# 1_P1.net
KiCad netlist of a schematic drawn in Altium Designer
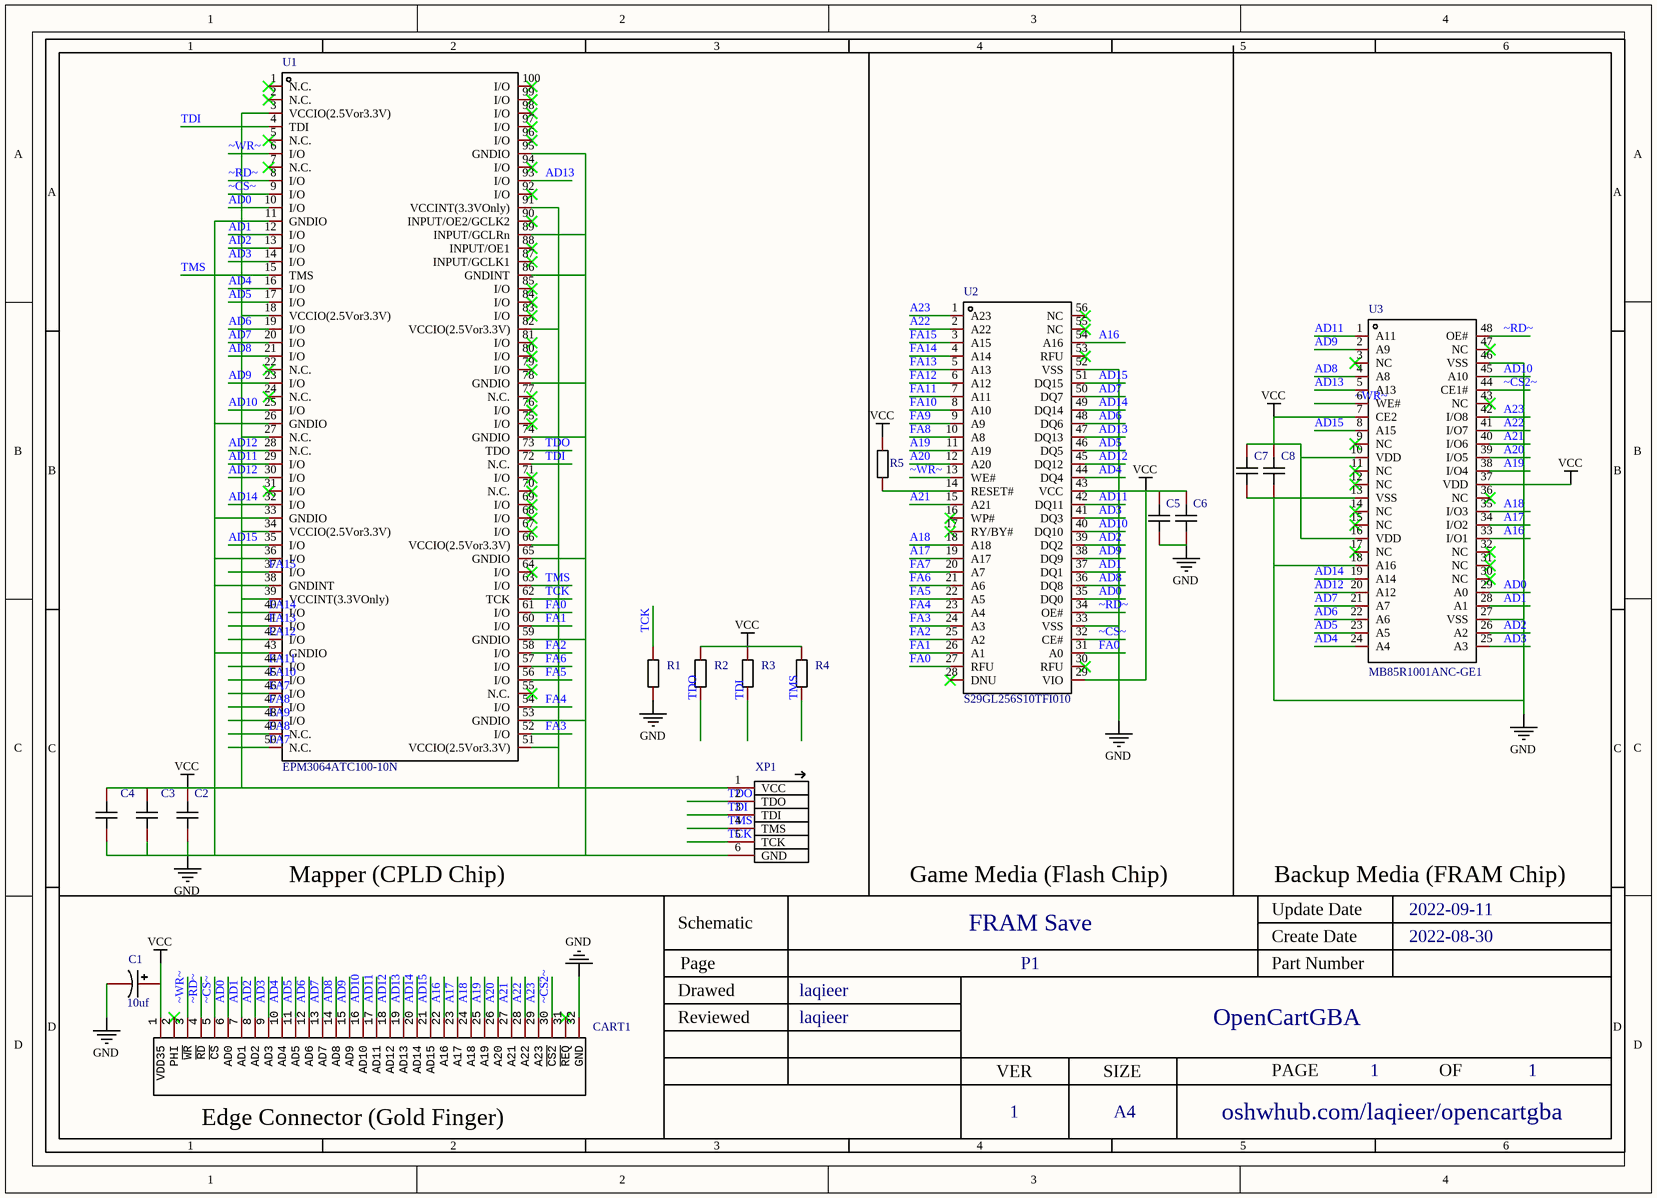
[diagram p0: 1_P1.schdoc]

(export (version "E")
  (design (tool "Eeschema 10.0.6"))
  (components
    (comp (ref "C1")
      (value "10uf")
      (fields (field (name "NAME") "10uf"))
      (libsource (lib "altium-import") (part "root_2_10uf_"))
    )
    (comp (ref "C2")
      (value "100nF/0603/50V")
      (libsource (lib "altium-import") (part "root_3_100nF/0603/50V_"))
    )
    (comp (ref "C3")
      (value "100nF/0603/50V")
      (libsource (lib "altium-import") (part "root_1_100nF/0603/50V_"))
    )
    (comp (ref "C4")
      (value "100nF/0603/50V")
      (libsource (lib "altium-import") (part "root_1_100nF/0603/50V_"))
    )
    (comp (ref "C5")
      (value "100nF/0603/50V")
      (libsource (lib "altium-import") (part "root_1_100nF/0603/50V_"))
    )
    (comp (ref "C6")
      (value "100nF/0603/50V")
      (libsource (lib "altium-import") (part "root_1_100nF/0603/50V_"))
    )
    (comp (ref "C7")
      (value "100nF/0603/50V")
      (libsource (lib "altium-import") (part "root_1_100nF/0603/50V_"))
    )
    (comp (ref "C8")
      (value "100nF/0603/50V")
      (libsource (lib "altium-import") (part "root_1_100nF/0603/50V_"))
    )
    (comp (ref "CART1")
      (value "GBACartridge")
      (description "GBA Cartridge")
      (libsource (lib "altium-import") (part "root_0_GBACartridge_"))
    )
    (comp (ref "R1")
      (value "10kω")
      (description "电阻类型:薄膜电阻;阻值:10kΩ;精度:±0.1%;功率:100mW;温度系数:±25ppm/;最大工作电压:75V;工作温度范围:-55~+155;")
      (fields
        (field (name "MANUFACTURER") "EVER OHMS(天二科技)")
        (field (name "MANUFACTURER PART") "TR0603B10K0P0525Z")
      )
      (libsource (lib "altium-import") (part "root_1_10kω_"))
    )
    (comp (ref "R2")
      (value "10kω")
      (description "电阻类型:薄膜电阻;阻值:10kΩ;精度:±0.1%;功率:100mW;温度系数:±25ppm/;最大工作电压:75V;工作温度范围:-55~+155;")
      (fields
        (field (name "MANUFACTURER") "EVER OHMS(天二科技)")
        (field (name "MANUFACTURER PART") "TR0603B10K0P0525Z")
      )
      (libsource (lib "altium-import") (part "root_1_10kω_"))
    )
    (comp (ref "R3")
      (value "10kω")
      (description "电阻类型:薄膜电阻;阻值:10kΩ;精度:±0.1%;功率:100mW;温度系数:±25ppm/;最大工作电压:75V;工作温度范围:-55~+155;")
      (fields
        (field (name "MANUFACTURER") "EVER OHMS(天二科技)")
        (field (name "MANUFACTURER PART") "TR0603B10K0P0525Z")
      )
      (libsource (lib "altium-import") (part "root_1_10kω_"))
    )
    (comp (ref "R4")
      (value "10kω")
      (description "电阻类型:薄膜电阻;阻值:10kΩ;精度:±0.1%;功率:100mW;温度系数:±25ppm/;最大工作电压:75V;工作温度范围:-55~+155;")
      (fields
        (field (name "MANUFACTURER") "EVER OHMS(天二科技)")
        (field (name "MANUFACTURER PART") "TR0603B10K0P0525Z")
      )
      (libsource (lib "altium-import") (part "root_1_10kω_"))
    )
    (comp (ref "R5")
      (value "10kω")
      (description "电阻类型:薄膜电阻;阻值:10kΩ;精度:±0.1%;功率:100mW;温度系数:±25ppm/;最大工作电压:75V;工作温度范围:-55~+155;")
      (fields
        (field (name "MANUFACTURER") "EVER OHMS(天二科技)")
        (field (name "MANUFACTURER PART") "TR0603B10K0P0525Z")
      )
      (libsource (lib "altium-import") (part "root_1_10kω_"))
    )
    (comp (ref "U1")
      (value "EPM3064ATC100-10N")
      (description "可编程类型:-;逻辑元件/块数:-;宏单元数:-;I/O 数:-;工作温度:-;")
      (fields (field (name "NAME") "EPM3064ATC100-10N") (field (name "MANUFACTURER") "Intel/Altera"))
      (libsource (lib "altium-import") (part "root_0_EPM3064ATC100-10N_"))
    )
    (comp (ref "U2")
      (value "S29GL256S10TFI010")
      (fields (field (name "NAME") "S29GL256S10TFI010") (field (name "MANUFACTURER") "SPANSION(飞索)"))
      (libsource (lib "altium-import") (part "root_0_S29GL256S10TFI010_"))
    )
    (comp (ref "U3")
      (value "MB85R1001ANC-GE1")
      (description "存储器容量:1Mb (128K x 8);存储器接口类型:Parallel;工作电压:3V ~ 3.6V;")
      (fields (field (name "NAME") "MB85R1001ANC-GE1") (field (name "MANUFACTURER") "FUJITSU(富士通)"))
      (libsource (lib "altium-import") (part "root_0_MB85R1001ANC-GE1_"))
    )
    (comp (ref "XP1") (value "jtag") (libsource (lib "altium-import") (part "root_0_jtag_")))
  )
  (nets
    (net (code "1") (name "/A16") (class "Default")
      (node (ref "CART1") (pin "22") (pinfunction "A16_22") (pintype "passive"))
      (node (ref "U2") (pin "54") (pinfunction "A16_54") (pintype "passive"))
      (node (ref "U3") (pin "33") (pinfunction "I/O1_33") (pintype "passive"))
    )
    (net (code "2") (name "/A17") (class "Default")
      (node (ref "CART1") (pin "23") (pinfunction "A17_23") (pintype "passive"))
      (node (ref "U2") (pin "19") (pinfunction "A17_19") (pintype "passive"))
      (node (ref "U3") (pin "34") (pinfunction "I/O2_34") (pintype "passive"))
    )
    (net (code "3") (name "/A18") (class "Default")
      (node (ref "CART1") (pin "24") (pinfunction "A18_24") (pintype "passive"))
      (node (ref "U2") (pin "18") (pinfunction "A18_18") (pintype "passive"))
      (node (ref "U3") (pin "35") (pinfunction "I/O3_35") (pintype "passive"))
    )
    (net (code "4") (name "/A19") (class "Default")
      (node (ref "CART1") (pin "25") (pinfunction "A19_25") (pintype "passive"))
      (node (ref "U2") (pin "11") (pinfunction "A19_11") (pintype "passive"))
      (node (ref "U3") (pin "38") (pinfunction "I/O4_38") (pintype "passive"))
    )
    (net (code "5") (name "/A20") (class "Default")
      (node (ref "CART1") (pin "26") (pinfunction "A20_26") (pintype "passive"))
      (node (ref "U2") (pin "12") (pinfunction "A20_12") (pintype "passive"))
      (node (ref "U3") (pin "39") (pinfunction "I/O5_39") (pintype "passive"))
    )
    (net (code "6") (name "/A21") (class "Default")
      (node (ref "CART1") (pin "27") (pinfunction "A21_27") (pintype "passive"))
      (node (ref "U2") (pin "15") (pinfunction "A21_15") (pintype "passive"))
      (node (ref "U3") (pin "40") (pinfunction "I/O6_40") (pintype "passive"))
    )
    (net (code "7") (name "/A22") (class "Default")
      (node (ref "CART1") (pin "28") (pinfunction "A22_28") (pintype "passive"))
      (node (ref "U2") (pin "2") (pinfunction "A22_2") (pintype "passive"))
      (node (ref "U3") (pin "41") (pinfunction "I/O7_41") (pintype "passive"))
    )
    (net (code "8") (name "/A23") (class "Default")
      (node (ref "CART1") (pin "29") (pinfunction "A23_29") (pintype "passive"))
      (node (ref "U2") (pin "1") (pinfunction "A23_1") (pintype "passive"))
      (node (ref "U3") (pin "42") (pinfunction "I/O8_42") (pintype "passive"))
    )
    (net (code "9") (name "/AD0") (class "Default")
      (node (ref "CART1") (pin "6") (pinfunction "AD0_6") (pintype "passive"))
      (node (ref "U1") (pin "10") (pinfunction "I/O_10") (pintype "passive"))
      (node (ref "U2") (pin "35") (pinfunction "DQ0_35") (pintype "passive"))
      (node (ref "U3") (pin "29") (pinfunction "A0_29") (pintype "passive"))
    )
    (net (code "10") (name "/AD1") (class "Default")
      (node (ref "CART1") (pin "7") (pinfunction "AD1_7") (pintype "passive"))
      (node (ref "U1") (pin "12") (pinfunction "I/O_12") (pintype "passive"))
      (node (ref "U2") (pin "37") (pinfunction "DQ1_37") (pintype "passive"))
      (node (ref "U3") (pin "28") (pinfunction "A1_28") (pintype "passive"))
    )
    (net (code "11") (name "/AD2") (class "Default")
      (node (ref "CART1") (pin "8") (pinfunction "AD2_8") (pintype "passive"))
      (node (ref "U1") (pin "13") (pinfunction "I/O_13") (pintype "passive"))
      (node (ref "U2") (pin "39") (pinfunction "DQ2_39") (pintype "passive"))
      (node (ref "U3") (pin "26") (pinfunction "A2_26") (pintype "passive"))
    )
    (net (code "12") (name "/AD3") (class "Default")
      (node (ref "CART1") (pin "9") (pinfunction "AD3_9") (pintype "passive"))
      (node (ref "U1") (pin "14") (pinfunction "I/O_14") (pintype "passive"))
      (node (ref "U2") (pin "41") (pinfunction "DQ3_41") (pintype "passive"))
      (node (ref "U3") (pin "25") (pinfunction "A3_25") (pintype "passive"))
    )
    (net (code "13") (name "/AD4") (class "Default")
      (node (ref "CART1") (pin "10") (pinfunction "AD4_10") (pintype "passive"))
      (node (ref "U1") (pin "16") (pinfunction "I/O_16") (pintype "passive"))
      (node (ref "U2") (pin "44") (pinfunction "DQ4_44") (pintype "passive"))
      (node (ref "U3") (pin "24") (pinfunction "A4_24") (pintype "passive"))
    )
    (net (code "14") (name "/AD5") (class "Default")
      (node (ref "CART1") (pin "11") (pinfunction "AD5_11") (pintype "passive"))
      (node (ref "U1") (pin "17") (pinfunction "I/O_17") (pintype "passive"))
      (node (ref "U2") (pin "46") (pinfunction "DQ5_46") (pintype "passive"))
      (node (ref "U3") (pin "23") (pinfunction "A5_23") (pintype "passive"))
    )
    (net (code "15") (name "/AD6") (class "Default")
      (node (ref "CART1") (pin "12") (pinfunction "AD6_12") (pintype "passive"))
      (node (ref "U1") (pin "19") (pinfunction "I/O_19") (pintype "passive"))
      (node (ref "U2") (pin "48") (pinfunction "DQ6_48") (pintype "passive"))
      (node (ref "U3") (pin "22") (pinfunction "A6_22") (pintype "passive"))
    )
    (net (code "16") (name "/AD7") (class "Default")
      (node (ref "CART1") (pin "13") (pinfunction "AD7_13") (pintype "passive"))
      (node (ref "U1") (pin "20") (pinfunction "I/O_20") (pintype "passive"))
      (node (ref "U2") (pin "50") (pinfunction "DQ7_50") (pintype "passive"))
      (node (ref "U3") (pin "21") (pinfunction "A7_21") (pintype "passive"))
    )
    (net (code "17") (name "/AD8") (class "Default")
      (node (ref "CART1") (pin "14") (pinfunction "AD8_14") (pintype "passive"))
      (node (ref "U1") (pin "21") (pinfunction "I/O_21") (pintype "passive"))
      (node (ref "U2") (pin "36") (pinfunction "DQ8_36") (pintype "passive"))
      (node (ref "U3") (pin "4") (pinfunction "A8_4") (pintype "passive"))
    )
    (net (code "18") (name "/AD9") (class "Default")
      (node (ref "CART1") (pin "15") (pinfunction "AD9_15") (pintype "passive"))
      (node (ref "U1") (pin "23") (pinfunction "I/O_23") (pintype "passive"))
      (node (ref "U2") (pin "38") (pinfunction "DQ9_38") (pintype "passive"))
      (node (ref "U3") (pin "2") (pinfunction "A9_2") (pintype "passive"))
    )
    (net (code "19") (name "/AD10") (class "Default")
      (node (ref "CART1") (pin "16") (pinfunction "AD10_16") (pintype "passive"))
      (node (ref "U1") (pin "25") (pinfunction "I/O_25") (pintype "passive"))
      (node (ref "U2") (pin "40") (pinfunction "DQ10_40") (pintype "passive"))
      (node (ref "U3") (pin "45") (pinfunction "A10_45") (pintype "passive"))
    )
    (net (code "20") (name "/AD11") (class "Default")
      (node (ref "CART1") (pin "17") (pinfunction "AD11_17") (pintype "passive"))
      (node (ref "U1") (pin "29") (pinfunction "I/O_29") (pintype "passive"))
      (node (ref "U2") (pin "42") (pinfunction "DQ11_42") (pintype "passive"))
      (node (ref "U3") (pin "1") (pinfunction "A11_1") (pintype "passive"))
    )
    (net (code "21") (name "/AD12") (class "Default")
      (node (ref "CART1") (pin "18") (pinfunction "AD12_18") (pintype "passive"))
      (node (ref "U1") (pin "28") (pinfunction "N.C._28") (pintype "passive"))
      (node (ref "U1") (pin "30") (pinfunction "I/O_30") (pintype "passive"))
      (node (ref "U2") (pin "45") (pinfunction "DQ12_45") (pintype "passive"))
      (node (ref "U3") (pin "20") (pinfunction "A12_20") (pintype "passive"))
    )
    (net (code "22") (name "/AD13") (class "Default")
      (node (ref "CART1") (pin "19") (pinfunction "AD13_19") (pintype "passive"))
      (node (ref "U1") (pin "93") (pinfunction "I/O_93") (pintype "passive"))
      (node (ref "U2") (pin "47") (pinfunction "DQ13_47") (pintype "passive"))
      (node (ref "U3") (pin "5") (pinfunction "A13_5") (pintype "passive"))
    )
    (net (code "23") (name "/AD14") (class "Default")
      (node (ref "CART1") (pin "20") (pinfunction "AD14_20") (pintype "passive"))
      (node (ref "U1") (pin "32") (pinfunction "I/O_32") (pintype "passive"))
      (node (ref "U2") (pin "49") (pinfunction "DQ14_49") (pintype "passive"))
      (node (ref "U3") (pin "19") (pinfunction "A14_19") (pintype "passive"))
    )
    (net (code "24") (name "/AD15") (class "Default")
      (node (ref "CART1") (pin "21") (pinfunction "AD15_21") (pintype "passive"))
      (node (ref "U1") (pin "35") (pinfunction "I/O_35") (pintype "passive"))
      (node (ref "U2") (pin "51") (pinfunction "DQ15_51") (pintype "passive"))
      (node (ref "U3") (pin "8") (pinfunction "A15_8") (pintype "passive"))
    )
    (net (code "25") (name "/FA0") (class "Default")
      (node (ref "U1") (pin "61") (pinfunction "I/O_61") (pintype "passive"))
      (node (ref "U2") (pin "27") (pinfunction "RFU_27") (pintype "passive"))
      (node (ref "U2") (pin "31") (pinfunction "A0_31") (pintype "passive"))
    )
    (net (code "26") (name "/FA1") (class "Default")
      (node (ref "U1") (pin "60") (pinfunction "I/O_60") (pintype "passive"))
      (node (ref "U2") (pin "26") (pinfunction "A1_26") (pintype "passive"))
    )
    (net (code "27") (name "/FA2") (class "Default")
      (node (ref "U1") (pin "58") (pinfunction "I/O_58") (pintype "passive"))
      (node (ref "U2") (pin "25") (pinfunction "A2_25") (pintype "passive"))
    )
    (net (code "28") (name "/FA3") (class "Default")
      (node (ref "U1") (pin "52") (pinfunction "I/O_52") (pintype "passive"))
      (node (ref "U2") (pin "24") (pinfunction "A3_24") (pintype "passive"))
    )
    (net (code "29") (name "/FA4") (class "Default")
      (node (ref "U1") (pin "54") (pinfunction "I/O_54") (pintype "passive"))
      (node (ref "U2") (pin "23") (pinfunction "A4_23") (pintype "passive"))
    )
    (net (code "30") (name "/FA5") (class "Default")
      (node (ref "U1") (pin "56") (pinfunction "I/O_56") (pintype "passive"))
      (node (ref "U2") (pin "22") (pinfunction "A5_22") (pintype "passive"))
    )
    (net (code "31") (name "/FA6") (class "Default")
      (node (ref "U1") (pin "57") (pinfunction "I/O_57") (pintype "passive"))
      (node (ref "U2") (pin "21") (pinfunction "A6_21") (pintype "passive"))
    )
    (net (code "32") (name "/FA7") (class "Default")
      (node (ref "U1") (pin "46") (pinfunction "I/O_46") (pintype "passive"))
      (node (ref "U1") (pin "50") (pinfunction "N.C._50") (pintype "passive"))
      (node (ref "U2") (pin "20") (pinfunction "A7_20") (pintype "passive"))
    )
    (net (code "33") (name "/FA8") (class "Default")
      (node (ref "U1") (pin "47") (pinfunction "I/O_47") (pintype "passive"))
      (node (ref "U1") (pin "49") (pinfunction "N.C._49") (pintype "passive"))
      (node (ref "U2") (pin "10") (pinfunction "A8_10") (pintype "passive"))
    )
    (net (code "34") (name "/FA9") (class "Default")
      (node (ref "U1") (pin "48") (pinfunction "I/O_48") (pintype "passive"))
      (node (ref "U2") (pin "9") (pinfunction "A9_9") (pintype "passive"))
    )
    (net (code "35") (name "/FA10") (class "Default")
      (node (ref "U1") (pin "45") (pinfunction "I/O_45") (pintype "passive"))
      (node (ref "U2") (pin "8") (pinfunction "A10_8") (pintype "passive"))
    )
    (net (code "36") (name "/FA11") (class "Default")
      (node (ref "U1") (pin "44") (pinfunction "I/O_44") (pintype "passive"))
      (node (ref "U2") (pin "7") (pinfunction "A11_7") (pintype "passive"))
    )
    (net (code "37") (name "/FA12") (class "Default")
      (node (ref "U1") (pin "42") (pinfunction "I/O_42") (pintype "passive"))
      (node (ref "U2") (pin "6") (pinfunction "A12_6") (pintype "passive"))
    )
    (net (code "38") (name "/FA13") (class "Default")
      (node (ref "U1") (pin "41") (pinfunction "I/O_41") (pintype "passive"))
      (node (ref "U2") (pin "5") (pinfunction "A13_5") (pintype "passive"))
    )
    (net (code "39") (name "/FA14") (class "Default")
      (node (ref "U1") (pin "40") (pinfunction "I/O_40") (pintype "passive"))
      (node (ref "U2") (pin "4") (pinfunction "A14_4") (pintype "passive"))
    )
    (net (code "40") (name "/FA15") (class "Default")
      (node (ref "U1") (pin "37") (pinfunction "I/O_37") (pintype "passive"))
      (node (ref "U2") (pin "3") (pinfunction "A15_3") (pintype "passive"))
    )
    (net (code "41") (name "/TCK") (class "Default")
      (node (ref "R1") (pin "2") (pinfunction "2_2") (pintype "passive"))
      (node (ref "U1") (pin "62") (pinfunction "TCK_62") (pintype "passive"))
      (node (ref "XP1") (pin "5") (pinfunction "TCK_5") (pintype "passive"))
    )
    (net (code "42") (name "/TDI") (class "Default")
      (node (ref "R3") (pin "1") (pinfunction "1_1") (pintype "passive"))
      (node (ref "U1") (pin "4") (pinfunction "TDI_4") (pintype "passive"))
      (node (ref "U1") (pin "72") (pinfunction "N.C._72") (pintype "passive"))
      (node (ref "XP1") (pin "3") (pinfunction "TDI_3") (pintype "passive"))
    )
    (net (code "43") (name "/TDO") (class "Default")
      (node (ref "R2") (pin "1") (pinfunction "1_1") (pintype "passive"))
      (node (ref "U1") (pin "73") (pinfunction "TDO_73") (pintype "passive"))
      (node (ref "XP1") (pin "2") (pinfunction "TDO_2") (pintype "passive"))
    )
    (net (code "44") (name "/TMS") (class "Default")
      (node (ref "R4") (pin "1") (pinfunction "1_1") (pintype "passive"))
      (node (ref "U1") (pin "15") (pinfunction "TMS_15") (pintype "passive"))
      (node (ref "U1") (pin "63") (pinfunction "I/O_63") (pintype "passive"))
      (node (ref "XP1") (pin "4") (pinfunction "TMS_4") (pintype "passive"))
    )
    (net (code "45") (name "/~CS2~") (class "Default")
      (node (ref "CART1") (pin "30") (pinfunction "~{CS2}_30") (pintype "passive"))
      (node (ref "U3") (pin "44") (pinfunction "CE1#_44") (pintype "passive"))
    )
    (net (code "46") (name "/~CS~") (class "Default")
      (node (ref "CART1") (pin "5") (pinfunction "~{CS}_5") (pintype "passive"))
      (node (ref "U1") (pin "9") (pinfunction "I/O_9") (pintype "passive"))
      (node (ref "U2") (pin "32") (pinfunction "CE#_32") (pintype "passive"))
    )
    (net (code "47") (name "/~RD~") (class "Default")
      (node (ref "CART1") (pin "4") (pinfunction "~{RD}_4") (pintype "passive"))
      (node (ref "U1") (pin "8") (pinfunction "I/O_8") (pintype "passive"))
      (node (ref "U2") (pin "34") (pinfunction "OE#_34") (pintype "passive"))
      (node (ref "U3") (pin "48") (pinfunction "OE#_48") (pintype "passive"))
    )
    (net (code "48") (name "/~WR~") (class "Default")
      (node (ref "CART1") (pin "3") (pinfunction "~{WR}_3") (pintype "passive"))
      (node (ref "U1") (pin "6") (pinfunction "I/O_6") (pintype "passive"))
      (node (ref "U2") (pin "13") (pinfunction "WE#_13") (pintype "passive"))
      (node (ref "U3") (pin "6") (pinfunction "WE#_6") (pintype "passive"))
    )
    (net (code "49") (name "GND") (class "Default")
      (node (ref "C1") (pin "2") (pinfunction "2_2") (pintype "passive"))
      (node (ref "C2") (pin "1") (pinfunction "1_1") (pintype "passive"))
      (node (ref "C3") (pin "2") (pinfunction "2_2") (pintype "passive"))
      (node (ref "C4") (pin "2") (pinfunction "2_2") (pintype "passive"))
      (node (ref "C5") (pin "2") (pinfunction "2_2") (pintype "passive"))
      (node (ref "C6") (pin "2") (pinfunction "2_2") (pintype "passive"))
      (node (ref "C7") (pin "2") (pinfunction "2_2") (pintype "passive"))
      (node (ref "C8") (pin "2") (pinfunction "2_2") (pintype "passive"))
      (node (ref "CART1") (pin "32") (pinfunction "GND_32") (pintype "passive"))
      (node (ref "R1") (pin "1") (pinfunction "1_1") (pintype "passive"))
      (node (ref "U1") (pin "11") (pinfunction "GNDIO_11") (pintype "passive"))
      (node (ref "U1") (pin "26") (pinfunction "GNDIO_26") (pintype "passive"))
      (node (ref "U1") (pin "33") (pinfunction "GNDIO_33") (pintype "passive"))
      (node (ref "U1") (pin "36") (pinfunction "I/O_36") (pintype "passive"))
      (node (ref "U1") (pin "38") (pinfunction "GNDINT_38") (pintype "passive"))
      (node (ref "U1") (pin "43") (pinfunction "GNDIO_43") (pintype "passive"))
      (node (ref "U1") (pin "53") (pinfunction "GNDIO_53") (pintype "passive"))
      (node (ref "U1") (pin "59") (pinfunction "GNDIO_59") (pintype "passive"))
      (node (ref "U1") (pin "65") (pinfunction "GNDIO_65") (pintype "passive"))
      (node (ref "U1") (pin "74") (pinfunction "GNDIO_74") (pintype "passive"))
      (node (ref "U1") (pin "78") (pinfunction "GNDIO_78") (pintype "passive"))
      (node (ref "U1") (pin "86") (pinfunction "GNDINT_86") (pintype "passive"))
      (node (ref "U1") (pin "89") (pinfunction "INPUT/GCLRn_89") (pintype "passive"))
      (node (ref "U1") (pin "95") (pinfunction "GNDIO_95") (pintype "passive"))
      (node (ref "U2") (pin "33") (pinfunction "VSS_33") (pintype "passive"))
      (node (ref "U2") (pin "52") (pinfunction "VSS_52") (pintype "passive"))
      (node (ref "U3") (pin "13") (pinfunction "VSS_13") (pintype "passive"))
      (node (ref "U3") (pin "18") (pinfunction "A16_18") (pintype "passive"))
      (node (ref "U3") (pin "27") (pinfunction "VSS_27") (pintype "passive"))
      (node (ref "U3") (pin "46") (pinfunction "VSS_46") (pintype "passive"))
      (node (ref "XP1") (pin "6") (pinfunction "GND_6") (pintype "passive"))
    )
    (net (code "50") (name "Net-(U2-RESET#)") (class "Default")
      (node (ref "R5") (pin "1") (pinfunction "1_1") (pintype "passive"))
      (node (ref "U2") (pin "14") (pinfunction "RESET#_14") (pintype "passive"))
    )
    (net (code "51") (name "VCC") (class "Default")
      (node (ref "C1") (pin "1") (pinfunction "1_1") (pintype "passive"))
      (node (ref "C2") (pin "2") (pinfunction "2_2") (pintype "passive"))
      (node (ref "C3") (pin "1") (pinfunction "1_1") (pintype "passive"))
      (node (ref "C4") (pin "1") (pinfunction "1_1") (pintype "passive"))
      (node (ref "C5") (pin "1") (pinfunction "1_1") (pintype "passive"))
      (node (ref "C6") (pin "1") (pinfunction "1_1") (pintype "passive"))
      (node (ref "C7") (pin "1") (pinfunction "1_1") (pintype "passive"))
      (node (ref "C8") (pin "1") (pinfunction "1_1") (pintype "passive"))
      (node (ref "CART1") (pin "1") (pinfunction "VDD35_1") (pintype "passive"))
      (node (ref "R2") (pin "2") (pinfunction "2_2") (pintype "passive"))
      (node (ref "R3") (pin "2") (pinfunction "2_2") (pintype "passive"))
      (node (ref "R4") (pin "2") (pinfunction "2_2") (pintype "passive"))
      (node (ref "R5") (pin "2") (pinfunction "2_2") (pintype "passive"))
      (node (ref "U1") (pin "18") (pinfunction "VCCIO(2.5Vor3.3V)_18") (pintype "passive"))
      (node (ref "U1") (pin "27") (pinfunction "N.C._27") (pintype "passive"))
      (node (ref "U1") (pin "3") (pinfunction "VCCIO(2.5Vor3.3V)_3") (pintype "passive"))
      (node (ref "U1") (pin "34") (pinfunction "VCCIO(2.5Vor3.3V)_34") (pintype "passive"))
      (node (ref "U1") (pin "39") (pinfunction "VCCINT(3.3VOnly)_39") (pintype "passive"))
      (node (ref "U1") (pin "51") (pinfunction "VCCIO(2.5Vor3.3V)_51") (pintype "passive"))
      (node (ref "U1") (pin "66") (pinfunction "VCCIO(2.5Vor3.3V)_66") (pintype "passive"))
      (node (ref "U1") (pin "82") (pinfunction "VCCIO(2.5Vor3.3V)_82") (pintype "passive"))
      (node (ref "U1") (pin "91") (pinfunction "VCCINT(3.3VOnly)_91") (pintype "passive"))
      (node (ref "U2") (pin "29") (pinfunction "VIO_29") (pintype "passive"))
      (node (ref "U2") (pin "43") (pinfunction "VCC_43") (pintype "passive"))
      (node (ref "U3") (pin "10") (pinfunction "VDD_10") (pintype "passive"))
      (node (ref "U3") (pin "16") (pinfunction "VDD_16") (pintype "passive"))
      (node (ref "U3") (pin "37") (pinfunction "VDD_37") (pintype "passive"))
      (node (ref "U3") (pin "7") (pinfunction "CE2_7") (pintype "passive"))
      (node (ref "XP1") (pin "1") (pinfunction "VCC_1") (pintype "passive"))
    )
    (net (code "52") (name "unconnected-(CART1-PHI-Pad2)") (class "Default")
      (node (ref "CART1") (pin "2") (pinfunction "PHI_2") (pintype "passive+no_connect"))
    )
    (net (code "53") (name "unconnected-(CART1-~{REQ}-Pad31)") (class "Default")
      (node (ref "CART1") (pin "31") (pinfunction "~{REQ}_31") (pintype "passive+no_connect"))
    )
    (net (code "54") (name "unconnected-(U1-INPUT{slash}GCLK1-Pad87)") (class "Default")
      (node (ref "U1") (pin "87") (pinfunction "INPUT/GCLK1_87") (pintype "passive+no_connect"))
    )
    (net (code "55") (name "unconnected-(U1-INPUT{slash}OE1-Pad88)") (class "Default")
      (node (ref "U1") (pin "88") (pinfunction "INPUT/OE1_88") (pintype "passive+no_connect"))
    )
    (net (code "56") (name "unconnected-(U1-INPUT{slash}OE2{slash}GCLK2-Pad90)") (class "Default")
      (node (ref "U1") (pin "90") (pinfunction "INPUT/OE2/GCLK2_90") (pintype "passive+no_connect"))
    )
    (net (code "57") (name "unconnected-(U1-I{slash}O-Pad31)") (class "Default")
      (node (ref "U1") (pin "31") (pinfunction "I/O_31") (pintype "passive+no_connect"))
    )
    (net (code "58") (name "unconnected-(U1-I{slash}O-Pad64)") (class "Default")
      (node (ref "U1") (pin "64") (pinfunction "I/O_64") (pintype "passive+no_connect"))
    )
    (net (code "59") (name "unconnected-(U1-I{slash}O-Pad67)") (class "Default")
      (node (ref "U1") (pin "67") (pinfunction "I/O_67") (pintype "passive+no_connect"))
    )
    (net (code "60") (name "unconnected-(U1-I{slash}O-Pad68)") (class "Default")
      (node (ref "U1") (pin "68") (pinfunction "I/O_68") (pintype "passive+no_connect"))
    )
    (net (code "61") (name "unconnected-(U1-I{slash}O-Pad69)") (class "Default")
      (node (ref "U1") (pin "69") (pinfunction "I/O_69") (pintype "passive+no_connect"))
    )
    (net (code "62") (name "unconnected-(U1-I{slash}O-Pad71)") (class "Default")
      (node (ref "U1") (pin "71") (pinfunction "I/O_71") (pintype "passive+no_connect"))
    )
    (net (code "63") (name "unconnected-(U1-I{slash}O-Pad75)") (class "Default")
      (node (ref "U1") (pin "75") (pinfunction "I/O_75") (pintype "passive+no_connect"))
    )
    (net (code "64") (name "unconnected-(U1-I{slash}O-Pad76)") (class "Default")
      (node (ref "U1") (pin "76") (pinfunction "I/O_76") (pintype "passive+no_connect"))
    )
    (net (code "65") (name "unconnected-(U1-I{slash}O-Pad79)") (class "Default")
      (node (ref "U1") (pin "79") (pinfunction "I/O_79") (pintype "passive+no_connect"))
    )
    (net (code "66") (name "unconnected-(U1-I{slash}O-Pad80)") (class "Default")
      (node (ref "U1") (pin "80") (pinfunction "I/O_80") (pintype "passive+no_connect"))
    )
    (net (code "67") (name "unconnected-(U1-I{slash}O-Pad81)") (class "Default")
      (node (ref "U1") (pin "81") (pinfunction "I/O_81") (pintype "passive+no_connect"))
    )
    (net (code "68") (name "unconnected-(U1-I{slash}O-Pad83)") (class "Default")
      (node (ref "U1") (pin "83") (pinfunction "I/O_83") (pintype "passive+no_connect"))
    )
    (net (code "69") (name "unconnected-(U1-I{slash}O-Pad84)") (class "Default")
      (node (ref "U1") (pin "84") (pinfunction "I/O_84") (pintype "passive+no_connect"))
    )
    (net (code "70") (name "unconnected-(U1-I{slash}O-Pad85)") (class "Default")
      (node (ref "U1") (pin "85") (pinfunction "I/O_85") (pintype "passive+no_connect"))
    )
    (net (code "71") (name "unconnected-(U1-I{slash}O-Pad92)") (class "Default")
      (node (ref "U1") (pin "92") (pinfunction "I/O_92") (pintype "passive+no_connect"))
    )
    (net (code "72") (name "unconnected-(U1-I{slash}O-Pad94)") (class "Default")
      (node (ref "U1") (pin "94") (pinfunction "I/O_94") (pintype "passive+no_connect"))
    )
    (net (code "73") (name "unconnected-(U1-I{slash}O-Pad96)") (class "Default")
      (node (ref "U1") (pin "96") (pinfunction "I/O_96") (pintype "passive+no_connect"))
    )
    (net (code "74") (name "unconnected-(U1-I{slash}O-Pad97)") (class "Default")
      (node (ref "U1") (pin "97") (pinfunction "I/O_97") (pintype "passive+no_connect"))
    )
    (net (code "75") (name "unconnected-(U1-I{slash}O-Pad98)") (class "Default")
      (node (ref "U1") (pin "98") (pinfunction "I/O_98") (pintype "passive+no_connect"))
    )
    (net (code "76") (name "unconnected-(U1-I{slash}O-Pad99)") (class "Default")
      (node (ref "U1") (pin "99") (pinfunction "I/O_99") (pintype "passive+no_connect"))
    )
    (net (code "77") (name "unconnected-(U1-I{slash}O-Pad100)") (class "Default")
      (node (ref "U1") (pin "100") (pinfunction "I/O_100") (pintype "passive+no_connect"))
    )
    (net (code "78") (name "unconnected-(U1-N.C.-Pad1)") (class "Default")
      (node (ref "U1") (pin "1") (pinfunction "N.C._1") (pintype "passive+no_connect"))
    )
    (net (code "79") (name "unconnected-(U1-N.C.-Pad2)") (class "Default")
      (node (ref "U1") (pin "2") (pinfunction "N.C._2") (pintype "passive+no_connect"))
    )
    (net (code "80") (name "unconnected-(U1-N.C.-Pad5)") (class "Default")
      (node (ref "U1") (pin "5") (pinfunction "N.C._5") (pintype "passive+no_connect"))
    )
    (net (code "81") (name "unconnected-(U1-N.C.-Pad7)") (class "Default")
      (node (ref "U1") (pin "7") (pinfunction "N.C._7") (pintype "passive+no_connect"))
    )
    (net (code "82") (name "unconnected-(U1-N.C.-Pad22)") (class "Default")
      (node (ref "U1") (pin "22") (pinfunction "N.C._22") (pintype "passive+no_connect"))
    )
    (net (code "83") (name "unconnected-(U1-N.C.-Pad24)") (class "Default")
      (node (ref "U1") (pin "24") (pinfunction "N.C._24") (pintype "passive+no_connect"))
    )
    (net (code "84") (name "unconnected-(U1-N.C.-Pad55)") (class "Default")
      (node (ref "U1") (pin "55") (pinfunction "N.C._55") (pintype "passive+no_connect"))
    )
    (net (code "85") (name "unconnected-(U1-N.C.-Pad70)") (class "Default")
      (node (ref "U1") (pin "70") (pinfunction "N.C._70") (pintype "passive+no_connect"))
    )
    (net (code "86") (name "unconnected-(U1-N.C.-Pad77)") (class "Default")
      (node (ref "U1") (pin "77") (pinfunction "N.C._77") (pintype "passive+no_connect"))
    )
    (net (code "87") (name "unconnected-(U2-DNU-Pad28)") (class "Default")
      (node (ref "U2") (pin "28") (pinfunction "DNU_28") (pintype "passive+no_connect"))
    )
    (net (code "88") (name "unconnected-(U2-NC-Pad55)") (class "Default")
      (node (ref "U2") (pin "55") (pinfunction "NC_55") (pintype "passive+no_connect"))
    )
    (net (code "89") (name "unconnected-(U2-NC-Pad56)") (class "Default")
      (node (ref "U2") (pin "56") (pinfunction "NC_56") (pintype "passive+no_connect"))
    )
    (net (code "90") (name "unconnected-(U2-RFU-Pad30)") (class "Default")
      (node (ref "U2") (pin "30") (pinfunction "RFU_30") (pintype "passive+no_connect"))
    )
    (net (code "91") (name "unconnected-(U2-RFU-Pad53)") (class "Default")
      (node (ref "U2") (pin "53") (pinfunction "RFU_53") (pintype "passive+no_connect"))
    )
    (net (code "92") (name "unconnected-(U2-RY{slash}BY#-Pad17)") (class "Default")
      (node (ref "U2") (pin "17") (pinfunction "RY/BY#_17") (pintype "passive+no_connect"))
    )
    (net (code "93") (name "unconnected-(U2-WP#-Pad16)") (class "Default")
      (node (ref "U2") (pin "16") (pinfunction "WP#_16") (pintype "passive+no_connect"))
    )
    (net (code "94") (name "unconnected-(U3-NC-Pad3)") (class "Default")
      (node (ref "U3") (pin "3") (pinfunction "NC_3") (pintype "passive+no_connect"))
    )
    (net (code "95") (name "unconnected-(U3-NC-Pad9)") (class "Default")
      (node (ref "U3") (pin "9") (pinfunction "NC_9") (pintype "passive+no_connect"))
    )
    (net (code "96") (name "unconnected-(U3-NC-Pad11)") (class "Default")
      (node (ref "U3") (pin "11") (pinfunction "NC_11") (pintype "passive+no_connect"))
    )
    (net (code "97") (name "unconnected-(U3-NC-Pad12)") (class "Default")
      (node (ref "U3") (pin "12") (pinfunction "NC_12") (pintype "passive+no_connect"))
    )
    (net (code "98") (name "unconnected-(U3-NC-Pad14)") (class "Default")
      (node (ref "U3") (pin "14") (pinfunction "NC_14") (pintype "passive+no_connect"))
    )
    (net (code "99") (name "unconnected-(U3-NC-Pad15)") (class "Default")
      (node (ref "U3") (pin "15") (pinfunction "NC_15") (pintype "passive+no_connect"))
    )
    (net (code "100") (name "unconnected-(U3-NC-Pad17)") (class "Default")
      (node (ref "U3") (pin "17") (pinfunction "NC_17") (pintype "passive+no_connect"))
    )
    (net (code "101") (name "unconnected-(U3-NC-Pad30)") (class "Default")
      (node (ref "U3") (pin "30") (pinfunction "NC_30") (pintype "passive+no_connect"))
    )
    (net (code "102") (name "unconnected-(U3-NC-Pad31)") (class "Default")
      (node (ref "U3") (pin "31") (pinfunction "NC_31") (pintype "passive+no_connect"))
    )
    (net (code "103") (name "unconnected-(U3-NC-Pad32)") (class "Default")
      (node (ref "U3") (pin "32") (pinfunction "NC_32") (pintype "passive+no_connect"))
    )
    (net (code "104") (name "unconnected-(U3-NC-Pad36)") (class "Default")
      (node (ref "U3") (pin "36") (pinfunction "NC_36") (pintype "passive+no_connect"))
    )
    (net (code "105") (name "unconnected-(U3-NC-Pad43)") (class "Default")
      (node (ref "U3") (pin "43") (pinfunction "NC_43") (pintype "passive+no_connect"))
    )
    (net (code "106") (name "unconnected-(U3-NC-Pad47)") (class "Default")
      (node (ref "U3") (pin "47") (pinfunction "NC_47") (pintype "passive+no_connect"))
    )
  )
)
